# PowerSupply.net
KiCad netlist of a schematic drawn in Altium Designer
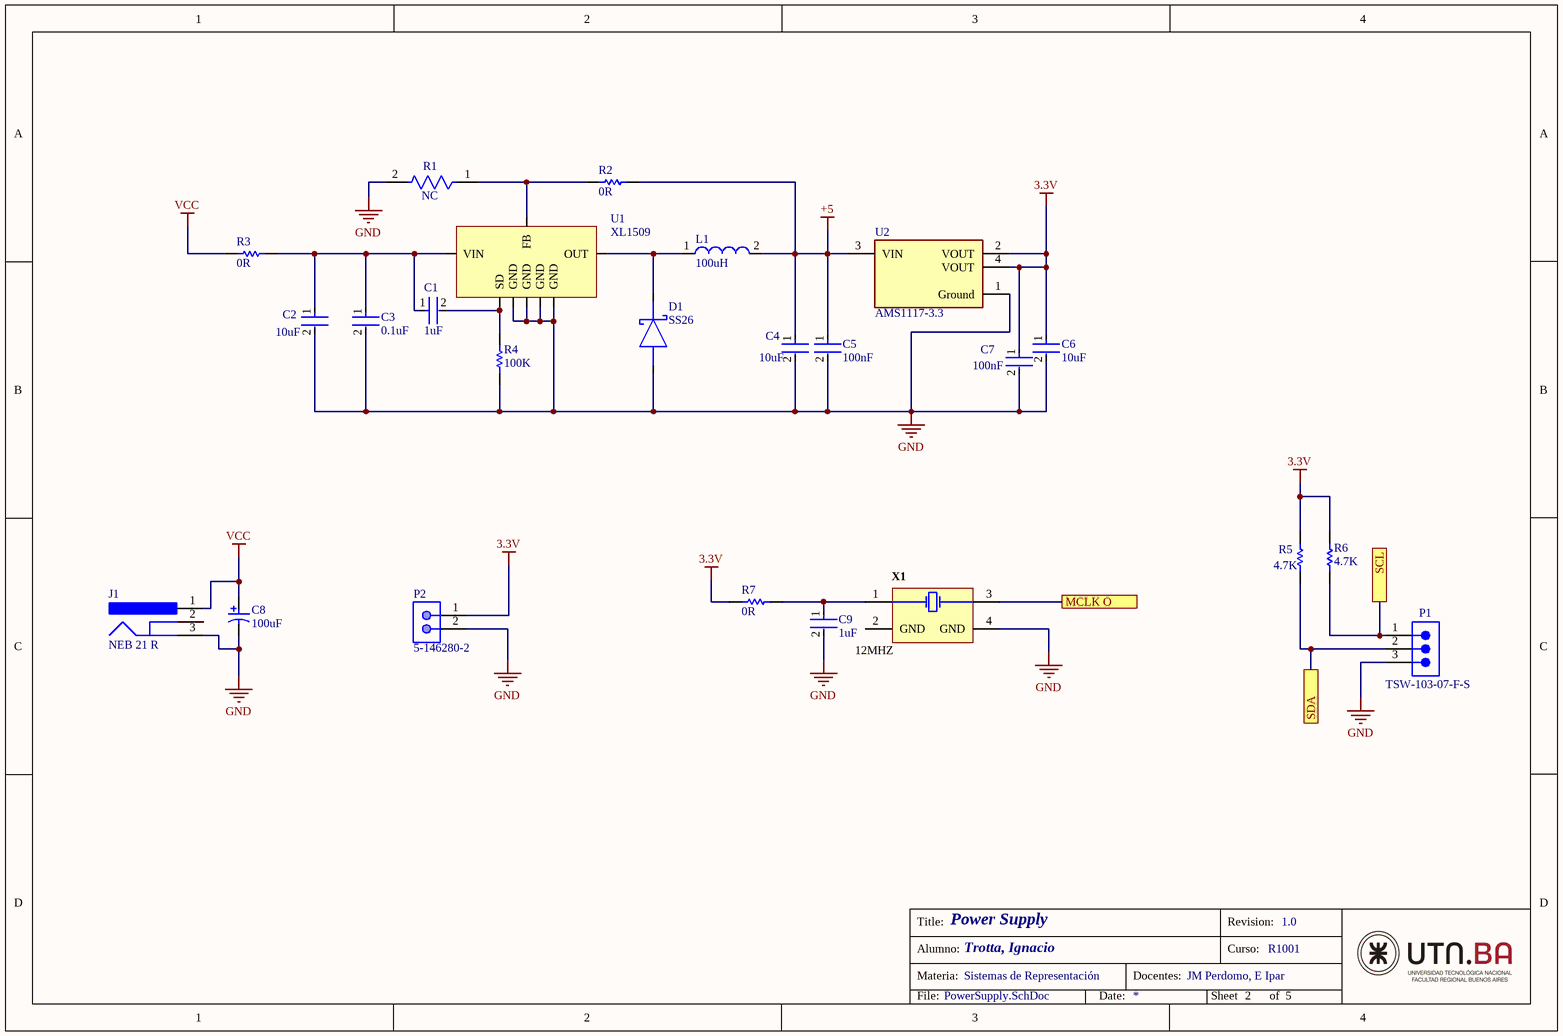
[diagram p0: PowerSupply.SchDoc]

(export (version "E")
  (design (tool "Eeschema 10.0.6"))
  (components
    (comp (ref "C1")
      (value "1uF")
      (footprint "FP-CC0603-DA-MFG")
      (description "CAP CER 10000PF 50V X7R 0603")
      (fields (field (name "TOLERANCE") "0.1") (field (name "MANUFACTURER PART NUMBER") "CC0603KRX7R9BB103"))
      (libsource (lib "Altium Content Vault") (part "11868f565c42a9108669ba33697ecf6"))
    )
    (comp (ref "C2")
      (value "10uF")
      (footprint "FP-CC1206-1_25-MFG")
      (description "CAP CER 0.1UF 50V X7R 1206")
      (fields
        (field (name "OCTOPART") "https://octopart.com/cc1206krx7r9bb104-yageo-39467816")
        (field (name "TOLERANCE") "0.1")
      )
      (libsource (lib "Altium Content Vault") (part "11868f565c42a9108669ba33697ecf6"))
    )
    (comp (ref "C3")
      (value "0.1uF")
      (footprint "FP-CC0603-DA-MFG")
      (description "CAP CER 10000PF 50V X7R 0603")
      (fields (field (name "TOLERANCE") "0.1") (field (name "MANUFACTURER PART NUMBER") "CC0603KRX7R9BB103"))
      (libsource (lib "Altium Content Vault") (part "11868f565c42a9108669ba33697ecf6"))
    )
    (comp (ref "C4")
      (value "10uF")
      (footprint "FP-CC1206-1_25-MFG")
      (description "CAP CER 0.1UF 50V X7R 1206")
      (fields
        (field (name "OCTOPART") "https://octopart.com/cc1206krx7r9bb104-yageo-39467816")
        (field (name "TOLERANCE") "0.1")
      )
      (libsource (lib "Altium Content Vault") (part "11868f565c42a9108669ba33697ecf6"))
    )
    (comp (ref "C5")
      (value "100nF")
      (footprint "FP-CC0603-DA-MFG")
      (description "CAP CER 10000PF 50V X7R 0603")
      (fields (field (name "TOLERANCE") "0.1") (field (name "MANUFACTURER PART NUMBER") "CC0603KRX7R9BB103"))
      (libsource (lib "Altium Content Vault") (part "11868f565c42a9108669ba33697ecf6"))
    )
    (comp (ref "C6")
      (value "10uF")
      (footprint "FP-CC0805-0_85-MFG")
      (description "CAP CER 0.1UF 50V X7R 0805")
      (fields (field (name "TOLERANCE") "0.1") (field (name "MANUFACTURER PART NUMBER") "CC0805KRX7R9BB104"))
      (libsource (lib "Altium Content Vault") (part "11868f565c42a9108669ba33697ecf6"))
    )
    (comp (ref "C7")
      (value "100nF")
      (footprint "FP-CC0603-DA-MFG")
      (description "CAP CER 10000PF 50V X7R 0603")
      (fields (field (name "TOLERANCE") "0.1") (field (name "MANUFACTURER PART NUMBER") "CC0603KRX7R9BB103"))
      (libsource (lib "Altium Content Vault") (part "11868f565c42a9108669ba33697ecf6"))
    )
    (comp (ref "C8")
      (value "100uF")
      (footprint "NIC-UCL1V101MNL1GS_L")
      (fields (field (name "MANUFACTURER") "Nichicon") (field (name "TOLERANCE") "20%"))
      (libsource (lib "Altium Content Vault") (part "CAP-P-2"))
    )
    (comp (ref "C9")
      (value "1uF")
      (footprint "FP-CC0603-DA-MFG")
      (description "CAP CER 10000PF 50V X7R 0603")
      (fields (field (name "TOLERANCE") "0.1") (field (name "MANUFACTURER PART NUMBER") "CC0603KRX7R9BB103"))
      (libsource (lib "Altium Content Vault") (part "11868f565c42a9108669ba33697ecf6"))
    )
    (comp (ref "D1")
      (value "SS26")
      (footprint "pcb-libs:SMB")
      (description "SCHOTTKY BARRIER\r\nRECTIFIER\r\n2.0 AMPERES\r\n60 VOLTS")
      (libsource (lib "sch-libs") (part "SS26_Trotta"))
    )
    (comp (ref "J1")
      (value "NEB 21 R")
      (footprint "LUMB-NEB21R_V")
      (description "Jack Socket, Body 14.5 x 9 mm, Height 11 mm, -20 to 70 degC, 3-Pin THD, RoHS, Bulk")
      (fields (field (name "MANUFACTURER") "Lumberg"))
      (libsource (lib "Altium Content Vault") (part "JACK-2CD3-RN"))
    )
    (comp (ref "L1")
      (value "100uH")
      (footprint "WE-PD2-M")
      (description "SMD Power Inductor WE-PD2, L = 100 µH")
      (libsource (lib "Altium Content Vault") (part "PAS-IND-INDUCTOR-2"))
    )
    (comp (ref "P1")
      (value "TSW-103-07-F-S")
      (footprint "SMTC-TSW-103-07-X-S")
      (description "0.025\" SQ Post Header, Through-hole, Vertical, -55 to 125 degC, 2.54 mm Pitch, 3-Pin, Male, RoHS")
      (fields (field (name "MANUFACTURER") "Samtec"))
      (libsource (lib "Altium Content Vault") (part "SMTC-TSW-103-X-X-S-X"))
    )
    (comp (ref "P2")
      (value "5-146280-2")
      (footprint "TECO-5-146280-2_V")
      (fields (field (name "MANUFACTURER") "TE Connectivity"))
      (libsource (lib "Altium Content Vault") (part "CN-1P-M-R2"))
    )
    (comp (ref "R1")
      (value "NC")
      (footprint "FP-RC2012-IPC_A")
      (description "Res Thick Film 0805 11.5kΩ 1% 0.125W ±100ppm/°C Molded SMD T/R")
      (fields (field (name "TOLERANCE") "1%"))
      (libsource (lib "Altium Content Vault") (part "1029c3af85768c4190bb7ad29bc67b5"))
    )
    (comp (ref "R2")
      (value "0R")
      (footprint "RESC1608X55X25ML10T15")
      (description "Chip Resistor, 100 Ohm, +/- 5%, 50 V, 0603 (1608 Metric), RoHS, Tape and Reel")
      (fields (field (name "MANUFACTURER") "Yageo") (field (name "TOLERANCE") "5%"))
      (libsource (lib "Altium Content Vault") (part "RES-2"))
    )
    (comp (ref "R3")
      (value "0R")
      (footprint "RESC1608X55X25ML10T15")
      (description "Chip Resistor, 100 Ohm, +/- 5%, 50 V, 0603 (1608 Metric), RoHS, Tape and Reel")
      (fields (field (name "MANUFACTURER") "Yageo") (field (name "TOLERANCE") "5%"))
      (libsource (lib "Altium Content Vault") (part "RES-2"))
    )
    (comp (ref "R4")
      (value "100K")
      (footprint "RESC1608X55X25ML10T15")
      (description "Chip Resistor, 100 Ohm, +/- 5%, 50 V, 0603 (1608 Metric), RoHS, Tape and Reel")
      (fields (field (name "MANUFACTURER") "Yageo") (field (name "TOLERANCE") "5%"))
      (libsource (lib "Altium Content Vault") (part "RES-2"))
    )
    (comp (ref "R5")
      (value "4.7K")
      (footprint "RESC1608X55X25ML10T15")
      (description "Chip Resistor, 4.7 KOhm, +/- 5%, 100 mW, -55 to 155 degC, 0603 (1608 Metric), RoHS, Tape and Reel")
      (fields (field (name "TOLERANCE") "5%") (field (name "MANUFACTURER") "Yageo"))
      (libsource (lib "Altium Content Vault") (part "RES-2"))
    )
    (comp (ref "R6")
      (value "4.7K")
      (footprint "RESC1608X55X25ML10T15")
      (description "Chip Resistor, 4.7 KOhm, +/- 5%, 100 mW, -55 to 155 degC, 0603 (1608 Metric), RoHS, Tape and Reel")
      (fields (field (name "TOLERANCE") "5%") (field (name "MANUFACTURER") "Yageo"))
      (libsource (lib "Altium Content Vault") (part "RES-2"))
    )
    (comp (ref "R7")
      (value "0R")
      (footprint "RESC1608X55X25ML10T15")
      (description "Chip Resistor, 100 Ohm, +/- 5%, 50 V, 0603 (1608 Metric), RoHS, Tape and Reel")
      (fields (field (name "MANUFACTURER") "Yageo") (field (name "TOLERANCE") "5%"))
      (libsource (lib "Altium Content Vault") (part "RES-2"))
    )
    (comp (ref "U1")
      (value "XL1509")
      (footprint "pcb-libs:SOIC8")
      (description "2A 150KHz 40V Buck DC to DC Converter")
      (libsource (lib "sch-libs") (part "XL1509_Trotta"))
    )
    (comp (ref "U2")
      (value "AMS1117-3.3")
      (footprint "FP-AMS1117-IPC_C")
      (description "LDO Voltage Regulators 1A, 3.3V")
      (fields
        (field (name "OCTOPART") "https://octopart.com/ams1117-3.3-advanced+monolithic+systems-25899300")
        (field (name "MANUFACTURER") "Advanced Monolithic Systems")
      )
      (libsource (lib "Altium Content Vault") (part "8bdbb5f8e77002000e30dd2845d0354"))
    )
    (comp (ref "X1")
      (value "12MHZ")
      (footprint "ABRACON_ABM8G_V")
      (fields (field (name "TOLERANCE") "20PPM") (field (name "MANUFACTURER") "ABRACON"))
      (libsource (lib "Altium Content Vault") (part "XTAL-1-3-4"))
    )
  )
  (nets
    (net (code "1") (name "+5") (class "Default")
      (node (ref "C4") (pin "1") (pinfunction "1_1") (pintype "passive"))
      (node (ref "C5") (pin "1") (pinfunction "1_1") (pintype "passive"))
      (node (ref "L1") (pin "2") (pinfunction "2_2") (pintype "passive"))
      (node (ref "R2") (pin "2") (pinfunction "2_2") (pintype "passive"))
      (node (ref "U2") (pin "3") (pinfunction "VIN_3") (pintype "power_in"))
    )
    (net (code "2") (name "/MCLK O") (class "Default")
      (node (ref "X1") (pin "3") (pinfunction "X2_3") (pintype "passive"))
    )
    (net (code "3") (name "/SCL") (class "Default")
      (node (ref "P1") (pin "1") (pinfunction "1_1") (pintype "passive"))
      (node (ref "R6") (pin "1") (pinfunction "1_1") (pintype "passive"))
    )
    (net (code "4") (name "/SDA") (class "Default")
      (node (ref "P1") (pin "2") (pinfunction "2_2") (pintype "passive"))
      (node (ref "R5") (pin "1") (pinfunction "1_1") (pintype "passive"))
    )
    (net (code "5") (name "3.3V") (class "Default")
      (node (ref "C6") (pin "1") (pinfunction "1_1") (pintype "passive"))
      (node (ref "C7") (pin "1") (pinfunction "1_1") (pintype "passive"))
      (node (ref "P2") (pin "1") (pinfunction "1_1") (pintype "passive"))
      (node (ref "R5") (pin "2") (pinfunction "2_2") (pintype "passive"))
      (node (ref "R6") (pin "2") (pinfunction "2_2") (pintype "passive"))
      (node (ref "R7") (pin "1") (pinfunction "1_1") (pintype "passive"))
      (node (ref "U2") (pin "2") (pinfunction "VOUT_2") (pintype "passive"))
      (node (ref "U2") (pin "4") (pinfunction "VOUT_4") (pintype "passive"))
    )
    (net (code "6") (name "GND") (class "Default")
      (node (ref "C2") (pin "2") (pinfunction "2_2") (pintype "passive"))
      (node (ref "C3") (pin "2") (pinfunction "2_2") (pintype "passive"))
      (node (ref "C4") (pin "2") (pinfunction "2_2") (pintype "passive"))
      (node (ref "C5") (pin "2") (pinfunction "2_2") (pintype "passive"))
      (node (ref "C6") (pin "2") (pinfunction "2_2") (pintype "passive"))
      (node (ref "C7") (pin "2") (pinfunction "2_2") (pintype "passive"))
      (node (ref "C8") (pin "2") (pinfunction "2_2") (pintype "passive"))
      (node (ref "C9") (pin "2") (pinfunction "2_2") (pintype "passive"))
      (node (ref "D1") (pin "A") (pinfunction "A_A") (pintype "passive"))
      (node (ref "J1") (pin "3") (pinfunction "3_3") (pintype "passive"))
      (node (ref "P1") (pin "3") (pinfunction "3_3") (pintype "passive"))
      (node (ref "P2") (pin "2") (pinfunction "2_2") (pintype "passive"))
      (node (ref "R1") (pin "2") (pinfunction "2_2") (pintype "passive"))
      (node (ref "R4") (pin "1") (pinfunction "1_1") (pintype "passive"))
      (node (ref "U1") (pin "5") (pinfunction "GND_5") (pintype "passive"))
      (node (ref "U1") (pin "6") (pinfunction "GND_6") (pintype "passive"))
      (node (ref "U1") (pin "7") (pinfunction "GND_7") (pintype "passive"))
      (node (ref "U1") (pin "8") (pinfunction "GND_8") (pintype "passive"))
      (node (ref "U2") (pin "1") (pinfunction "Ground_1") (pintype "power_in"))
      (node (ref "X1") (pin "4") (pinfunction "GND_4") (pintype "power_in"))
    )
    (net (code "7") (name "Net-(D1-K)") (class "Default")
      (node (ref "D1") (pin "C") (pinfunction "K_C") (pintype "passive"))
      (node (ref "L1") (pin "1") (pinfunction "1_1") (pintype "passive"))
      (node (ref "U1") (pin "2") (pinfunction "OUT_2") (pintype "passive"))
    )
    (net (code "8") (name "Net-(U1-FB)") (class "Default")
      (node (ref "R1") (pin "1") (pinfunction "1_1") (pintype "passive"))
      (node (ref "R2") (pin "1") (pinfunction "1_1") (pintype "passive"))
      (node (ref "U1") (pin "3") (pinfunction "FB_3") (pintype "passive"))
    )
    (net (code "9") (name "Net-(U1-SD)") (class "Default")
      (node (ref "C1") (pin "2") (pinfunction "2_2") (pintype "passive"))
      (node (ref "R4") (pin "2") (pinfunction "2_2") (pintype "passive"))
      (node (ref "U1") (pin "4") (pinfunction "SD_4") (pintype "passive"))
    )
    (net (code "10") (name "Net-(U1-VIN)") (class "Default")
      (node (ref "C1") (pin "1") (pinfunction "1_1") (pintype "passive"))
      (node (ref "C2") (pin "1") (pinfunction "1_1") (pintype "passive"))
      (node (ref "C3") (pin "1") (pinfunction "1_1") (pintype "passive"))
      (node (ref "R3") (pin "2") (pinfunction "2_2") (pintype "passive"))
      (node (ref "U1") (pin "1") (pinfunction "VIN_1") (pintype "passive"))
    )
    (net (code "11") (name "Net-(X1-X1)") (class "Default")
      (node (ref "C9") (pin "1") (pinfunction "1_1") (pintype "passive"))
      (node (ref "R7") (pin "2") (pinfunction "2_2") (pintype "passive"))
      (node (ref "X1") (pin "1") (pinfunction "X1_1") (pintype "passive"))
    )
    (net (code "12") (name "VCC") (class "Default")
      (node (ref "C8") (pin "1") (pinfunction "1_1") (pintype "passive"))
      (node (ref "J1") (pin "1") (pinfunction "1_1") (pintype "passive"))
      (node (ref "R3") (pin "1") (pinfunction "1_1") (pintype "passive"))
    )
    (net (code "13") (name "unconnected-(J1-Pad2)") (class "Default")
      (node (ref "J1") (pin "2") (pinfunction "2_2") (pintype "passive"))
    )
    (net (code "14") (name "unconnected-(X1-GND-Pad2)") (class "Default")
      (node (ref "X1") (pin "2") (pinfunction "GND_2") (pintype "power_in"))
    )
  )
)
